# MCU.net
KiCad netlist of a schematic drawn in Altium Designer
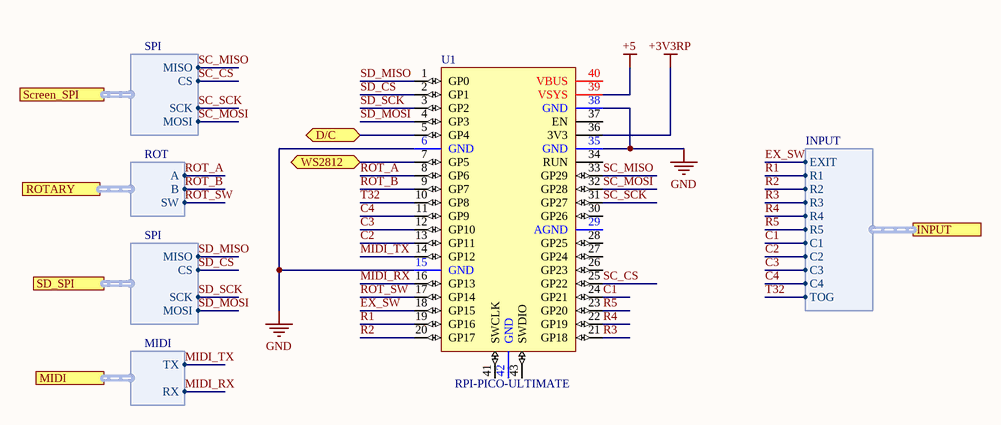
[diagram p0: MCU.SchDoc]

(export (version "E")
  (design (tool "Eeschema 10.0.6"))
  (components
    (comp (ref "U1")
      (value "RPI-PICO-ULTIMATE")
      (footprint "Pico_Headers:SAMTEC SSW-110-03-T-S")
      (description "RASPBERRY PI PICO RP2040 BOARD NO TEST PADS")
      (fields
        (field (name "MANUFACTURER") "Raspberry Pi Foundation")
        (field (name "MANUFACTURER PART NO") "SC0915")
      )
      (libsource (lib "RPi_Pico") (part "RPI-PICO-MOD_SM"))
    )
  )
  (nets
    (net (code "5") (name "+3V3RP") (class "Default")
      (node (ref "U1") (pin "36") (pinfunction "3V3_36") (pintype "power_in"))
    )
    (net (code "6") (name "+5") (class "Default")
      (node (ref "U1") (pin "39") (pinfunction "VSYS_39") (pintype "power_in"))
    )
    (net (code "7") (name "/C1") (class "Default")
      (node (ref "U1") (pin "24") (pinfunction "GP21_24") (pintype "bidirectional"))
    )
    (net (code "8") (name "/C2") (class "Default")
      (node (ref "U1") (pin "13") (pinfunction "GP11_13") (pintype "bidirectional"))
    )
    (net (code "9") (name "/C3") (class "Default")
      (node (ref "U1") (pin "12") (pinfunction "GP10_12") (pintype "bidirectional"))
    )
    (net (code "10") (name "/C4") (class "Default")
      (node (ref "U1") (pin "11") (pinfunction "GP9_11") (pintype "bidirectional"))
    )
    (net (code "11") (name "/D{slash}C") (class "Default")
      (node (ref "U1") (pin "5") (pinfunction "GP4_5") (pintype "bidirectional"))
    )
    (net (code "12") (name "/EX_SW") (class "Default")
      (node (ref "U1") (pin "18") (pinfunction "GP15_18") (pintype "bidirectional"))
    )
    (net (code "13") (name "/MIDI_RX") (class "Default")
      (node (ref "U1") (pin "16") (pinfunction "GP13_16") (pintype "bidirectional"))
    )
    (net (code "14") (name "/MIDI_TX") (class "Default")
      (node (ref "U1") (pin "14") (pinfunction "GP12_14") (pintype "bidirectional"))
    )
    (net (code "15") (name "/R1") (class "Default")
      (node (ref "U1") (pin "19") (pinfunction "GP16_19") (pintype "bidirectional"))
    )
    (net (code "16") (name "/R2") (class "Default")
      (node (ref "U1") (pin "20") (pinfunction "GP17_20") (pintype "bidirectional"))
    )
    (net (code "17") (name "/R3") (class "Default")
      (node (ref "U1") (pin "21") (pinfunction "GP18_21") (pintype "bidirectional"))
    )
    (net (code "18") (name "/R4") (class "Default")
      (node (ref "U1") (pin "22") (pinfunction "GP19_22") (pintype "bidirectional"))
    )
    (net (code "19") (name "/R5") (class "Default")
      (node (ref "U1") (pin "23") (pinfunction "GP20_23") (pintype "bidirectional"))
    )
    (net (code "20") (name "/ROT_A") (class "Default")
      (node (ref "U1") (pin "8") (pinfunction "GP6_8") (pintype "bidirectional"))
    )
    (net (code "21") (name "/ROT_B") (class "Default")
      (node (ref "U1") (pin "9") (pinfunction "GP7_9") (pintype "bidirectional"))
    )
    (net (code "22") (name "/ROT_SW") (class "Default")
      (node (ref "U1") (pin "17") (pinfunction "GP14_17") (pintype "bidirectional"))
    )
    (net (code "23") (name "/SC_CS") (class "Default")
      (node (ref "U1") (pin "25") (pinfunction "GP22_25") (pintype "bidirectional"))
    )
    (net (code "24") (name "/SC_MISO") (class "Default")
      (node (ref "U1") (pin "33") (pinfunction "GP29_33") (pintype "bidirectional"))
    )
    (net (code "25") (name "/SC_MOSI") (class "Default")
      (node (ref "U1") (pin "32") (pinfunction "GP28_32") (pintype "bidirectional"))
    )
    (net (code "26") (name "/SC_SCK") (class "Default")
      (node (ref "U1") (pin "31") (pinfunction "GP27_31") (pintype "bidirectional"))
    )
    (net (code "27") (name "/SD_CS") (class "Default")
      (node (ref "U1") (pin "2") (pinfunction "GP1_2") (pintype "bidirectional"))
    )
    (net (code "28") (name "/SD_MISO") (class "Default")
      (node (ref "U1") (pin "1") (pinfunction "GP0_1") (pintype "bidirectional"))
    )
    (net (code "29") (name "/SD_MOSI") (class "Default")
      (node (ref "U1") (pin "4") (pinfunction "GP3_4") (pintype "bidirectional"))
    )
    (net (code "30") (name "/SD_SCK") (class "Default")
      (node (ref "U1") (pin "3") (pinfunction "GP2_3") (pintype "bidirectional"))
    )
    (net (code "31") (name "/T32") (class "Default")
      (node (ref "U1") (pin "10") (pinfunction "GP8_10") (pintype "bidirectional"))
    )
    (net (code "32") (name "/WS2812") (class "Default")
      (node (ref "U1") (pin "7") (pinfunction "GP5_7") (pintype "bidirectional"))
    )
    (net (code "37") (name "GND") (class "Default")
      (node (ref "U1") (pin "15") (pinfunction "GND_15") (pintype "power_in"))
      (node (ref "U1") (pin "35") (pinfunction "GND_35") (pintype "power_in"))
      (node (ref "U1") (pin "38") (pinfunction "GND_38") (pintype "power_in"))
      (node (ref "U1") (pin "6") (pinfunction "GND_6") (pintype "power_in"))
    )
    (net (code "38") (name "unconnected-(U1-AGND-Pad29)") (class "Default")
      (node (ref "U1") (pin "29") (pinfunction "AGND_29") (pintype "power_in"))
    )
    (net (code "39") (name "unconnected-(U1-EN-Pad37)") (class "Default")
      (node (ref "U1") (pin "37") (pinfunction "EN_37") (pintype "passive"))
    )
    (net (code "40") (name "unconnected-(U1-GND-Pad42)") (class "Default")
      (node (ref "U1") (pin "42") (pinfunction "GND_42") (pintype "power_in"))
    )
    (net (code "41") (name "unconnected-(U1-GP23-Pad26)") (class "Default")
      (node (ref "U1") (pin "26") (pinfunction "GP23_26") (pintype "bidirectional"))
    )
    (net (code "42") (name "unconnected-(U1-GP24-Pad27)") (class "Default")
      (node (ref "U1") (pin "27") (pinfunction "GP24_27") (pintype "bidirectional"))
    )
    (net (code "43") (name "unconnected-(U1-GP25-Pad28)") (class "Default")
      (node (ref "U1") (pin "28") (pinfunction "GP25_28") (pintype "bidirectional"))
    )
    (net (code "44") (name "unconnected-(U1-GP26-Pad30)") (class "Default")
      (node (ref "U1") (pin "30") (pinfunction "GP26_30") (pintype "bidirectional"))
    )
    (net (code "45") (name "unconnected-(U1-RUN-Pad34)") (class "Default")
      (node (ref "U1") (pin "34") (pinfunction "RUN_34") (pintype "passive"))
    )
    (net (code "46") (name "unconnected-(U1-SWCLK-Pad41)") (class "Default")
      (node (ref "U1") (pin "41") (pinfunction "SWCLK_41") (pintype "bidirectional"))
    )
    (net (code "47") (name "unconnected-(U1-SWDIO-Pad43)") (class "Default")
      (node (ref "U1") (pin "43") (pinfunction "SWDIO_43") (pintype "bidirectional"))
    )
    (net (code "48") (name "unconnected-(U1-VBUS-Pad40)") (class "Default")
      (node (ref "U1") (pin "40") (pinfunction "VBUS_40") (pintype "power_in"))
    )
  )
)
